# PM12_P3V8.net
KiCad netlist of a schematic drawn in Altium Designer
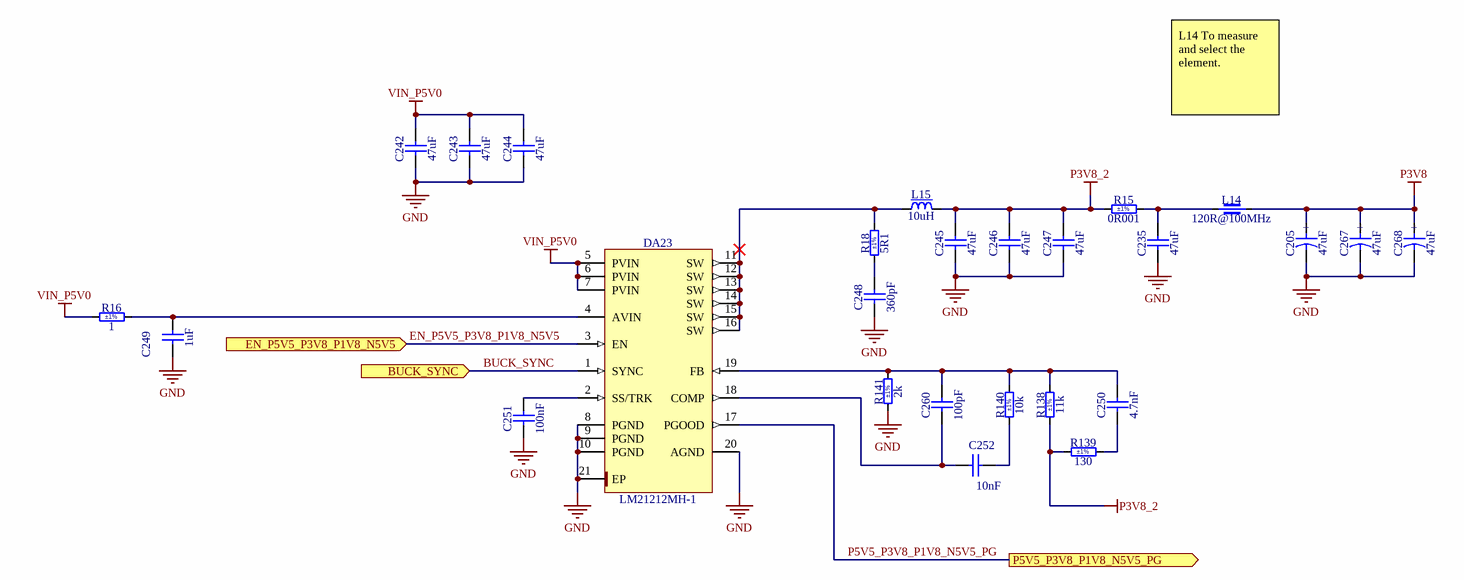
[diagram p0: PM12_P3V8.SchDoc]

(export (version "E")
  (design (tool "Eeschema 10.0.6"))
  (components
    (comp (ref "C205")
      (value "47uF")
      (footprint "CAPAE530X610N")
      (description "Polarised capacitor")
      (fields
        (field (name "PART NUMBER") "CAE530-610_47UF_16V_20%")
        (field (name "VOLTAGE") "16V")
        (field (name "AUTHOR") "CERN DEM HF")
      )
      (libsource (lib "Capacitors") (part "Capacitor - polarized"))
    )
    (comp (ref "C235")
      (value "47uF")
      (footprint "CAPC3225X270N")
      (description "Non-polarised capacitor")
      (fields
        (field (name "PART NUMBER") "CC1210_47UF_16V_20%_X5R")
        (field (name "VOLTAGE") "16V")
        (field (name "AUTHOR") "CERN DEM MR")
      )
      (libsource (lib "Capacitors") (part "Capacitor - non polarized"))
    )
    (comp (ref "C242")
      (value "47uF")
      (footprint "CAPC3225X270N")
      (description "Non-polarised capacitor")
      (fields
        (field (name "PART NUMBER") "CC1210_47UF_16V_20%_X5R")
        (field (name "VOLTAGE") "16V")
        (field (name "AUTHOR") "CERN DEM MR")
      )
      (libsource (lib "Capacitors") (part "Capacitor - non polarized"))
    )
    (comp (ref "C243")
      (value "47uF")
      (footprint "CAPC3225X270N")
      (description "Non-polarised capacitor")
      (fields
        (field (name "PART NUMBER") "CC1210_47UF_16V_20%_X5R")
        (field (name "VOLTAGE") "16V")
        (field (name "AUTHOR") "CERN DEM MR")
      )
      (libsource (lib "Capacitors") (part "Capacitor - non polarized"))
    )
    (comp (ref "C244")
      (value "47uF")
      (footprint "CAPC3225X270N")
      (description "Non-polarised capacitor")
      (fields
        (field (name "PART NUMBER") "CC1210_47UF_16V_20%_X5R")
        (field (name "VOLTAGE") "16V")
        (field (name "AUTHOR") "CERN DEM MR")
      )
      (libsource (lib "Capacitors") (part "Capacitor - non polarized"))
    )
    (comp (ref "C245")
      (value "47uF")
      (footprint "CAPC3225X270N")
      (description "Non-polarised capacitor")
      (fields
        (field (name "PART NUMBER") "CC1210_47UF_16V_20%_X5R")
        (field (name "VOLTAGE") "16V")
        (field (name "AUTHOR") "CERN DEM MR")
      )
      (libsource (lib "Capacitors") (part "Capacitor - non polarized"))
    )
    (comp (ref "C246")
      (value "47uF")
      (footprint "CAPC3225X270N")
      (description "Non-polarised capacitor")
      (fields
        (field (name "PART NUMBER") "CC1210_47UF_16V_20%_X5R")
        (field (name "VOLTAGE") "16V")
        (field (name "AUTHOR") "CERN DEM MR")
      )
      (libsource (lib "Capacitors") (part "Capacitor - non polarized"))
    )
    (comp (ref "C247")
      (value "47uF")
      (footprint "CAPC3225X270N")
      (description "Non-polarised capacitor")
      (fields
        (field (name "PART NUMBER") "CC1210_47UF_16V_20%_X5R")
        (field (name "VOLTAGE") "16V")
        (field (name "AUTHOR") "CERN DEM MR")
      )
      (libsource (lib "Capacitors") (part "Capacitor - non polarized"))
    )
    (comp (ref "C248")
      (value "360pF")
      (footprint "CAPC2013X145N")
      (description "Non-polarised capacitor")
      (fields
        (field (name "PART NUMBER") "CC0805_360PF_50V_5%_C0G")
        (field (name "VOLTAGE") "50V")
        (field (name "AUTHOR") "CERN DEM HF")
      )
      (libsource (lib "Capacitors") (part "Capacitor - non polarized"))
    )
    (comp (ref "C249")
      (value "1uF")
      (footprint "CAPC2012X140N")
      (description "Non-polarised capacitor")
      (fields
        (field (name "PART NUMBER") "CC0805_1UF_25V_10%_X7R")
        (field (name "VOLTAGE") "25V")
        (field (name "AUTHOR") "CERN DEM JLC")
      )
      (libsource (lib "Capacitors") (part "Capacitor - non polarized"))
    )
    (comp (ref "C250")
      (value "4.7nF")
      (footprint "CAPC2012X135N")
      (description "Non-polarised capacitor")
      (fields
        (field (name "PART NUMBER") "CC0805_4.7NF_50V_10%_X7R")
        (field (name "VOLTAGE") "50V")
        (field (name "AUTHOR") "CERN DEM JLC")
      )
      (libsource (lib "Capacitors") (part "Capacitor - non polarized"))
    )
    (comp (ref "C251")
      (value "100nF")
      (footprint "CAPC2012X135N")
      (description "Non-polarised capacitor")
      (fields
        (field (name "PART NUMBER") "CC0805_100NF_50V_10%_X7R")
        (field (name "VOLTAGE") "50V")
        (field (name "AUTHOR") "CERN DEM JLC")
      )
      (libsource (lib "Capacitors") (part "Capacitor - non polarized"))
    )
    (comp (ref "C252")
      (value "10nF")
      (footprint "CAPC1005X55N")
      (description "Non-polarised capacitor")
      (fields
        (field (name "PART NUMBER") "CC0402_10NF_25V_10%_X7R")
        (field (name "VOLTAGE") "25V")
        (field (name "AUTHOR") "CERN DEM JLC")
      )
      (libsource (lib "Capacitors") (part "Capacitor - non polarized"))
    )
    (comp (ref "C260")
      (value "100pF")
      (footprint "CAPC2012X135N")
      (description "Non-polarised capacitor")
      (fields
        (field (name "PART NUMBER") "CC0805_100PF_50V_5%_NP0")
        (field (name "VOLTAGE") "50V")
        (field (name "AUTHOR") "CERN DEM JLC")
      )
      (libsource (lib "Capacitors") (part "Capacitor - non polarized"))
    )
    (comp (ref "C267")
      (value "47uF")
      (footprint "CAPAE530X610N")
      (description "Polarised capacitor")
      (fields
        (field (name "PART NUMBER") "CAE530-610_47UF_16V_20%")
        (field (name "VOLTAGE") "16V")
        (field (name "AUTHOR") "CERN DEM HF")
      )
      (libsource (lib "Capacitors") (part "Capacitor - polarized"))
    )
    (comp (ref "C268")
      (value "47uF")
      (footprint "CAPAE530X610N")
      (description "Polarised capacitor")
      (fields
        (field (name "PART NUMBER") "CAE530-610_47UF_16V_20%")
        (field (name "VOLTAGE") "16V")
        (field (name "AUTHOR") "CERN DEM HF")
      )
      (libsource (lib "Capacitors") (part "Capacitor - polarized"))
    )
    (comp (ref "DA23")
      (value "LM21212MH-1")
      (footprint "TEXAS_PWP0020AA")
      (description "2.95-V To 5.5-V, 12-A, Voltage-Mode Synchronous Buck Regulator with Frequency Synchronization")
      (fields (field (name "MANUFACTURER") "TEXAS INSTRUMENTS") (field (name "AUTHOR") "CERN DEM HF"))
      (libsource (lib "ICs And Semiconductors") (part "LM21212"))
    )
    (comp (ref "L14")
      (value "120R@100MHz")
      (footprint "IND_MURATA_BLM31KN")
      (fields
        (field (name "PART NUMBER") "IND1206_MURATA_BLM31KN121SN1")
        (field (name "POWER") "6A")
        (field (name "TOLERANCE") "±25%")
        (field (name "AUTHOR") "CERN DEM HF")
      )
      (libsource (lib "Inductors & Transformers") (part "Ferrite Bead"))
    )
    (comp (ref "L15")
      (value "10uH")
      (footprint "IND_VISHAY_IHPL4040DZ-01")
      (description "Inductor With Core")
      (fields
        (field (name "PART NUMBER") "IND4040_10UH_20%_VISHAY_IHLP-4040DZ-01")
        (field (name "POWER") "6.8A")
        (field (name "AUTHOR") "CERN DEM HF")
      )
      (libsource (lib "Inductors & Transformers") (part "Inductor With Magnetic core"))
    )
    (comp (ref "R15")
      (value "0R001")
      (footprint "RESC_BOURNS_CRE2512_0R001-0R004")
      (description "Resistor - 1%")
      (fields
        (field (name "TOLERANCE") "±1%")
        (field (name "PART NUMBER") "R2512_0R001_1%_3W_50PPM_BOURNS_CRE2512")
        (field (name "POWER") "3W")
        (field (name "AUTHOR") "CERN DEM BC")
      )
      (libsource (lib "Resistors") (part "Resistor - 1%"))
    )
    (comp (ref "R16")
      (value "1")
      (footprint "RESC2012X60N")
      (description "Resistor - 1%")
      (fields
        (field (name "TOLERANCE") "±1%")
        (field (name "PART NUMBER") "R0805_1R_1%_0.125W_100PPM")
        (field (name "POWER") "0.125W")
        (field (name "AUTHOR") "CERN DEM HF")
      )
      (libsource (lib "Resistors") (part "Resistor - 1%"))
    )
    (comp (ref "R18")
      (value "5R1")
      (footprint "RESC2012X60N")
      (description "Resistor - 1%")
      (fields
        (field (name "TOLERANCE") "±1%")
        (field (name "PART NUMBER") "R0805_5R1_1%_0.125W_100PPM")
        (field (name "POWER") "0.125W")
        (field (name "AUTHOR") "CERN DEM HF")
      )
      (libsource (lib "Resistors") (part "Resistor - 1%"))
    )
    (comp (ref "R138")
      (value "11k")
      (footprint "RESC2012X60N")
      (description "Resistor - 1%")
      (fields
        (field (name "TOLERANCE") "±1%")
        (field (name "PART NUMBER") "R0805_11K_1%_0.125W_100PPM")
        (field (name "POWER") "0.125W")
        (field (name "AUTHOR") "CERN DEM JLC")
      )
      (libsource (lib "Resistors") (part "Resistor - 1%"))
    )
    (comp (ref "R139")
      (value "130")
      (footprint "RESC2012X60N")
      (description "Resistor - 1%")
      (fields
        (field (name "TOLERANCE") "±1%")
        (field (name "PART NUMBER") "R0805_130R_1%_0.125W_100PPM")
        (field (name "POWER") "0.125W")
        (field (name "AUTHOR") "CERN DEM JLC")
      )
      (libsource (lib "Resistors") (part "Resistor - 1%"))
    )
    (comp (ref "R140")
      (value "10k")
      (footprint "RESC1608X55N")
      (description "Resistor - 1%")
      (fields
        (field (name "TOLERANCE") "±1%")
        (field (name "PART NUMBER") "R0603_10K_1%_0.1W_100PPM")
        (field (name "POWER") "0.1W")
        (field (name "AUTHOR") "CERN DEM JLC")
      )
      (libsource (lib "Resistors") (part "Resistor - 1%"))
    )
    (comp (ref "R141")
      (value "2k")
      (footprint "RESC2012X60N")
      (description "Resistor - 1%")
      (fields
        (field (name "TOLERANCE") "±1%")
        (field (name "PART NUMBER") "R0805_2K_1%_0.125W_100PPM")
        (field (name "POWER") "0.125W")
        (field (name "AUTHOR") "CERN DEM JLC")
      )
      (libsource (lib "Resistors") (part "Resistor - 1%"))
    )
  )
  (nets
    (net (code "1") (name "/BUCK_SYNC") (class "Default")
      (node (ref "DA23") (pin "1") (pinfunction "SYNC_1") (pintype "input"))
    )
    (net (code "2") (name "/EN_P5V5_P3V8_P1V8_N5V5") (class "Default")
      (node (ref "DA23") (pin "3") (pinfunction "EN_3") (pintype "input"))
    )
    (net (code "3") (name "/P5V5_P3V8_P1V8_N5V5_PG") (class "Default")
      (node (ref "DA23") (pin "17") (pinfunction "PGOOD_17") (pintype "output"))
    )
    (net (code "4") (name "GND") (class "Default")
      (node (ref "C205") (pin "2") (pinfunction "2_2") (pintype "passive"))
      (node (ref "C235") (pin "1") (pinfunction "1_1") (pintype "passive"))
      (node (ref "C242") (pin "1") (pinfunction "1_1") (pintype "passive"))
      (node (ref "C243") (pin "1") (pinfunction "1_1") (pintype "passive"))
      (node (ref "C244") (pin "1") (pinfunction "1_1") (pintype "passive"))
      (node (ref "C245") (pin "1") (pinfunction "1_1") (pintype "passive"))
      (node (ref "C246") (pin "1") (pinfunction "1_1") (pintype "passive"))
      (node (ref "C247") (pin "1") (pinfunction "1_1") (pintype "passive"))
      (node (ref "C248") (pin "1") (pinfunction "1_1") (pintype "passive"))
      (node (ref "C249") (pin "1") (pinfunction "1_1") (pintype "passive"))
      (node (ref "C251") (pin "1") (pinfunction "1_1") (pintype "passive"))
      (node (ref "C267") (pin "2") (pinfunction "2_2") (pintype "passive"))
      (node (ref "C268") (pin "2") (pinfunction "2_2") (pintype "passive"))
      (node (ref "DA23") (pin "10") (pinfunction "PGND_10") (pintype "power_in"))
      (node (ref "DA23") (pin "20") (pinfunction "AGND_20") (pintype "power_in"))
      (node (ref "DA23") (pin "21") (pinfunction "EP_21") (pintype "power_in"))
      (node (ref "DA23") (pin "8") (pinfunction "PGND_8") (pintype "power_in"))
      (node (ref "DA23") (pin "9") (pinfunction "PGND_9") (pintype "power_in"))
      (node (ref "R141") (pin "1") (pinfunction "1_1") (pintype "passive"))
    )
    (net (code "5") (name "Net-(C235-Pad2)") (class "Default")
      (node (ref "C235") (pin "2") (pinfunction "2_2") (pintype "passive"))
      (node (ref "L14") (pin "1") (pinfunction "1_1") (pintype "passive"))
      (node (ref "R15") (pin "2") (pinfunction "2_2") (pintype "passive"))
    )
    (net (code "6") (name "Net-(C248-Pad2)") (class "Default")
      (node (ref "C248") (pin "2") (pinfunction "2_2") (pintype "passive"))
      (node (ref "R18") (pin "1") (pinfunction "1_1") (pintype "passive"))
    )
    (net (code "7") (name "Net-(C250-Pad1)") (class "Default")
      (node (ref "C250") (pin "1") (pinfunction "1_1") (pintype "passive"))
      (node (ref "R139") (pin "1") (pinfunction "1_1") (pintype "passive"))
    )
    (net (code "8") (name "Net-(C252-Pad1)") (class "Default")
      (node (ref "C252") (pin "1") (pinfunction "1_1") (pintype "passive"))
      (node (ref "R140") (pin "1") (pinfunction "1_1") (pintype "passive"))
    )
    (net (code "9") (name "Net-(DA23-AVIN)") (class "Default")
      (node (ref "C249") (pin "2") (pinfunction "2_2") (pintype "passive"))
      (node (ref "DA23") (pin "4") (pinfunction "AVIN_4") (pintype "power_in"))
      (node (ref "R16") (pin "2") (pinfunction "2_2") (pintype "passive"))
    )
    (net (code "10") (name "Net-(DA23-COMP)") (class "Default")
      (node (ref "C252") (pin "2") (pinfunction "2_2") (pintype "passive"))
      (node (ref "C260") (pin "1") (pinfunction "1_1") (pintype "passive"))
      (node (ref "DA23") (pin "18") (pinfunction "COMP_18") (pintype "output"))
    )
    (net (code "11") (name "Net-(DA23-FB)") (class "Default")
      (node (ref "C250") (pin "2") (pinfunction "2_2") (pintype "passive"))
      (node (ref "C260") (pin "2") (pinfunction "2_2") (pintype "passive"))
      (node (ref "DA23") (pin "19") (pinfunction "FB_19") (pintype "input"))
      (node (ref "R138") (pin "2") (pinfunction "2_2") (pintype "passive"))
      (node (ref "R140") (pin "2") (pinfunction "2_2") (pintype "passive"))
      (node (ref "R141") (pin "2") (pinfunction "2_2") (pintype "passive"))
    )
    (net (code "12") (name "Net-(DA23-SS{slash}TRK)") (class "Default")
      (node (ref "C251") (pin "2") (pinfunction "2_2") (pintype "passive"))
      (node (ref "DA23") (pin "2") (pinfunction "SS/TRK_2") (pintype "input"))
    )
    (net (code "13") (name "Net-(DA23-SW-Pad11)") (class "Default")
      (node (ref "DA23") (pin "11") (pinfunction "SW_11") (pintype "output"))
      (node (ref "DA23") (pin "12") (pinfunction "SW_12") (pintype "output"))
      (node (ref "DA23") (pin "13") (pinfunction "SW_13") (pintype "output"))
      (node (ref "DA23") (pin "14") (pinfunction "SW_14") (pintype "output"))
      (node (ref "DA23") (pin "15") (pinfunction "SW_15") (pintype "output"))
      (node (ref "DA23") (pin "16") (pinfunction "SW_16") (pintype "output"))
      (node (ref "L15") (pin "1") (pinfunction "1_1") (pintype "passive"))
      (node (ref "R18") (pin "2") (pinfunction "2_2") (pintype "passive"))
    )
    (net (code "14") (name "P3V8") (class "Default")
      (node (ref "C205") (pin "1") (pinfunction "1_1") (pintype "passive"))
      (node (ref "C267") (pin "1") (pinfunction "1_1") (pintype "passive"))
      (node (ref "C268") (pin "1") (pinfunction "1_1") (pintype "passive"))
      (node (ref "L14") (pin "2") (pinfunction "2_2") (pintype "passive"))
    )
    (net (code "15") (name "P3V8_2") (class "Default")
      (node (ref "C245") (pin "2") (pinfunction "2_2") (pintype "passive"))
      (node (ref "C246") (pin "2") (pinfunction "2_2") (pintype "passive"))
      (node (ref "C247") (pin "2") (pinfunction "2_2") (pintype "passive"))
      (node (ref "L15") (pin "2") (pinfunction "2_2") (pintype "passive"))
      (node (ref "R138") (pin "1") (pinfunction "1_1") (pintype "passive"))
      (node (ref "R139") (pin "2") (pinfunction "2_2") (pintype "passive"))
      (node (ref "R15") (pin "1") (pinfunction "1_1") (pintype "passive"))
    )
    (net (code "16") (name "VIN_P5V0") (class "Default")
      (node (ref "C242") (pin "2") (pinfunction "2_2") (pintype "passive"))
      (node (ref "C243") (pin "2") (pinfunction "2_2") (pintype "passive"))
      (node (ref "C244") (pin "2") (pinfunction "2_2") (pintype "passive"))
      (node (ref "DA23") (pin "5") (pinfunction "PVIN_5") (pintype "power_in"))
      (node (ref "DA23") (pin "6") (pinfunction "PVIN_6") (pintype "power_in"))
      (node (ref "DA23") (pin "7") (pinfunction "PVIN_7") (pintype "power_in"))
      (node (ref "R16") (pin "1") (pinfunction "1_1") (pintype "passive"))
    )
  )
)
